# IV9.net
KiCad netlist of a schematic drawn in EAGLE
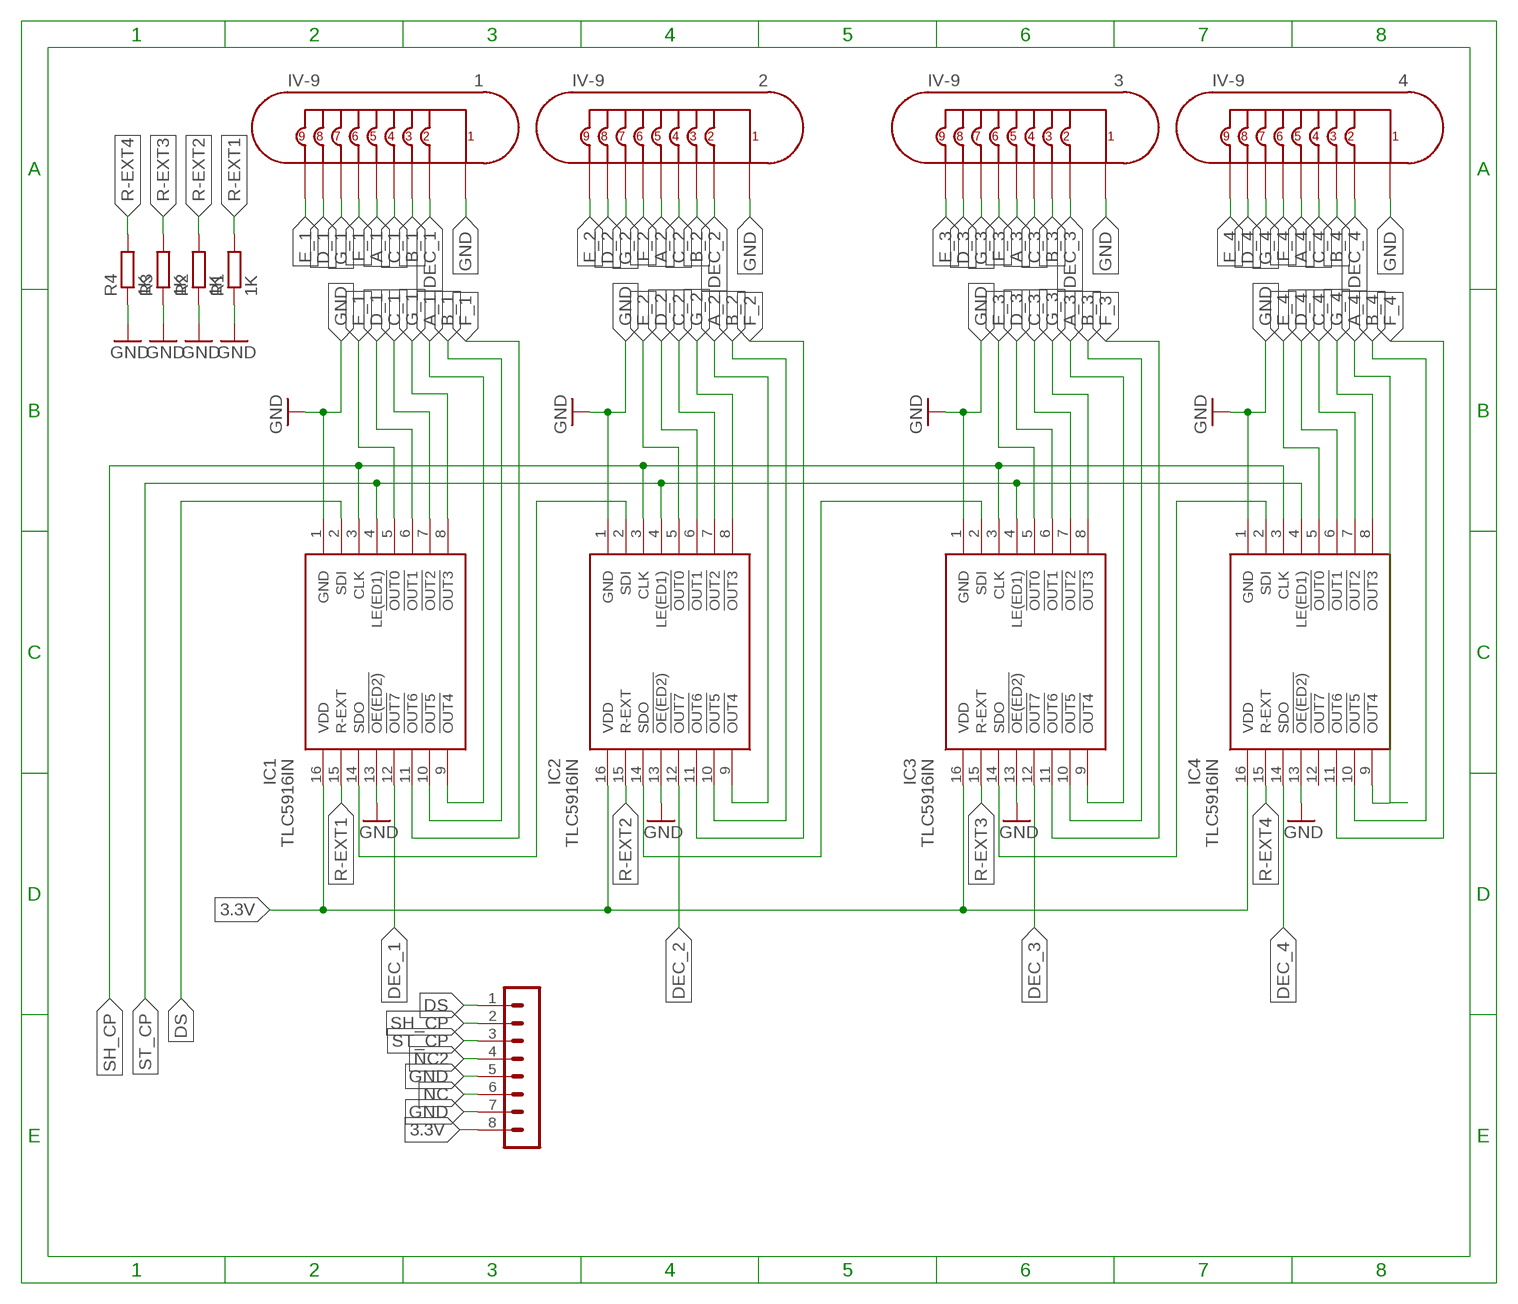
[diagram p0: schematic, sheet 1]

(export (version "E")
  (design (tool "Eeschema 10.0.6"))
  (components
    (comp (ref "1")
      (value "IV-9")
      (footprint "eagle-import:IV-9")
      (libsource (lib "eagle-import") (part "IV-9"))
    )
    (comp (ref "2")
      (value "IV-9")
      (footprint "eagle-import:IV-9")
      (libsource (lib "eagle-import") (part "IV-9"))
    )
    (comp (ref "3")
      (value "IV-9")
      (footprint "eagle-import:IV-9")
      (libsource (lib "eagle-import") (part "IV-9"))
    )
    (comp (ref "4")
      (value "IV-9")
      (footprint "eagle-import:IV-9")
      (libsource (lib "eagle-import") (part "IV-9"))
    )
    (comp (ref "IC1")
      (value "TLC5916IN")
      (footprint "eagle-import:DIP794W53P254L1930H508Q16N")
      (fields (field (name "MOUSER_PART_NUMBER") "595-TLC5916IN"))
      (libsource (lib "eagle-import") (part "TLC5916IN"))
    )
    (comp (ref "IC2")
      (value "TLC5916IN")
      (footprint "eagle-import:DIP794W53P254L1930H508Q16N")
      (fields (field (name "MOUSER_PART_NUMBER") "595-TLC5916IN"))
      (libsource (lib "eagle-import") (part "TLC5916IN"))
    )
    (comp (ref "IC3")
      (value "TLC5916IN")
      (footprint "eagle-import:DIP794W53P254L1930H508Q16N")
      (fields (field (name "MOUSER_PART_NUMBER") "595-TLC5916IN"))
      (libsource (lib "eagle-import") (part "TLC5916IN"))
    )
    (comp (ref "IC4")
      (value "TLC5916IN")
      (footprint "eagle-import:DIP794W53P254L1930H508Q16N")
      (fields (field (name "MOUSER_PART_NUMBER") "595-TLC5916IN"))
      (libsource (lib "eagle-import") (part "TLC5916IN"))
    )
    (comp (ref "R1")
      (value "1K")
      (footprint "eagle-import:R1206")
      (libsource (lib "eagle-import") (part "R-EU_R1206"))
    )
    (comp (ref "R2")
      (value "1K")
      (footprint "eagle-import:R1206")
      (libsource (lib "eagle-import") (part "R-EU_R1206"))
    )
    (comp (ref "R3")
      (value "1K")
      (footprint "eagle-import:R1206")
      (libsource (lib "eagle-import") (part "R-EU_R1206"))
    )
    (comp (ref "R4")
      (value "1K")
      (footprint "eagle-import:R1206")
      (libsource (lib "eagle-import") (part "R-EU_R1206"))
    )
    (comp (ref "SV2")
      (value "PINHEADER-1X8")
      (footprint "eagle-import:MA08-1")
      (libsource (lib "eagle-import") (part "PINHEADER-1X8"))
    )
  )
  (nets
    (net (code "1") (name "3.3V") (class "Default")
      (node (ref "IC1") (pin "16") (pinfunction "VDD_16") (pintype "bidirectional"))
      (node (ref "IC2") (pin "16") (pinfunction "VDD_16") (pintype "bidirectional"))
      (node (ref "IC3") (pin "16") (pinfunction "VDD_16") (pintype "bidirectional"))
      (node (ref "IC4") (pin "16") (pinfunction "VDD_16") (pintype "bidirectional"))
      (node (ref "SV2") (pin "8") (pinfunction "8_8") (pintype "passive"))
    )
    (net (code "2") (name "A_1") (class "Default")
      (node (ref "1") (pin "5") (pinfunction "5_5") (pintype "bidirectional"))
      (node (ref "IC1") (pin "9") (pinfunction "~{OUT4}_9") (pintype "bidirectional"))
    )
    (net (code "3") (name "A_2") (class "Default")
      (node (ref "2") (pin "5") (pinfunction "5_5") (pintype "bidirectional"))
      (node (ref "IC2") (pin "9") (pinfunction "~{OUT4}_9") (pintype "bidirectional"))
    )
    (net (code "4") (name "A_3") (class "Default")
      (node (ref "3") (pin "5") (pinfunction "5_5") (pintype "bidirectional"))
      (node (ref "IC3") (pin "9") (pinfunction "~{OUT4}_9") (pintype "bidirectional"))
    )
    (net (code "5") (name "A_4") (class "Default")
      (node (ref "4") (pin "5") (pinfunction "5_5") (pintype "bidirectional"))
      (node (ref "IC4") (pin "9") (pinfunction "~{OUT4}_9") (pintype "bidirectional"))
    )
    (net (code "6") (name "B_1") (class "Default")
      (node (ref "1") (pin "3") (pinfunction "3_3") (pintype "bidirectional"))
      (node (ref "IC1") (pin "10") (pinfunction "~{OUT5}_10") (pintype "bidirectional"))
    )
    (net (code "7") (name "B_2") (class "Default")
      (node (ref "2") (pin "3") (pinfunction "3_3") (pintype "bidirectional"))
      (node (ref "IC2") (pin "10") (pinfunction "~{OUT5}_10") (pintype "bidirectional"))
    )
    (net (code "8") (name "B_3") (class "Default")
      (node (ref "3") (pin "3") (pinfunction "3_3") (pintype "bidirectional"))
      (node (ref "IC3") (pin "10") (pinfunction "~{OUT5}_10") (pintype "bidirectional"))
    )
    (net (code "9") (name "B_4") (class "Default")
      (node (ref "4") (pin "3") (pinfunction "3_3") (pintype "bidirectional"))
      (node (ref "IC4") (pin "10") (pinfunction "~{OUT5}_10") (pintype "bidirectional"))
    )
    (net (code "10") (name "C_1") (class "Default")
      (node (ref "1") (pin "4") (pinfunction "4_4") (pintype "bidirectional"))
      (node (ref "IC1") (pin "7") (pinfunction "~{OUT2}_7") (pintype "bidirectional"))
    )
    (net (code "11") (name "C_2") (class "Default")
      (node (ref "2") (pin "4") (pinfunction "4_4") (pintype "bidirectional"))
      (node (ref "IC2") (pin "7") (pinfunction "~{OUT2}_7") (pintype "bidirectional"))
    )
    (net (code "12") (name "C_3") (class "Default")
      (node (ref "3") (pin "4") (pinfunction "4_4") (pintype "bidirectional"))
      (node (ref "IC3") (pin "7") (pinfunction "~{OUT2}_7") (pintype "bidirectional"))
    )
    (net (code "13") (name "C_4") (class "Default")
      (node (ref "4") (pin "4") (pinfunction "4_4") (pintype "bidirectional"))
      (node (ref "IC4") (pin "7") (pinfunction "~{OUT2}_7") (pintype "bidirectional"))
    )
    (net (code "14") (name "DEC_1") (class "Default")
      (node (ref "1") (pin "2") (pinfunction "2_2") (pintype "bidirectional"))
      (node (ref "IC1") (pin "12") (pinfunction "~{OUT7}_12") (pintype "bidirectional"))
    )
    (net (code "15") (name "DEC_2") (class "Default")
      (node (ref "2") (pin "2") (pinfunction "2_2") (pintype "bidirectional"))
      (node (ref "IC2") (pin "12") (pinfunction "~{OUT7}_12") (pintype "bidirectional"))
    )
    (net (code "16") (name "DEC_3") (class "Default")
      (node (ref "3") (pin "2") (pinfunction "2_2") (pintype "bidirectional"))
      (node (ref "IC3") (pin "12") (pinfunction "~{OUT7}_12") (pintype "bidirectional"))
    )
    (net (code "17") (name "DEC_4") (class "Default")
      (node (ref "4") (pin "2") (pinfunction "2_2") (pintype "bidirectional"))
      (node (ref "IC4") (pin "14") (pinfunction "SDO_14") (pintype "bidirectional"))
    )
    (net (code "18") (name "DS") (class "Default")
      (node (ref "IC1") (pin "2") (pinfunction "SDI_2") (pintype "bidirectional"))
      (node (ref "SV2") (pin "1") (pinfunction "1_1") (pintype "passive"))
    )
    (net (code "19") (name "D_1") (class "Default")
      (node (ref "1") (pin "8") (pinfunction "8_8") (pintype "bidirectional"))
      (node (ref "IC1") (pin "6") (pinfunction "~{OUT1}_6") (pintype "bidirectional"))
    )
    (net (code "20") (name "D_2") (class "Default")
      (node (ref "2") (pin "8") (pinfunction "8_8") (pintype "bidirectional"))
      (node (ref "IC2") (pin "6") (pinfunction "~{OUT1}_6") (pintype "bidirectional"))
    )
    (net (code "21") (name "D_3") (class "Default")
      (node (ref "3") (pin "8") (pinfunction "8_8") (pintype "bidirectional"))
      (node (ref "IC3") (pin "6") (pinfunction "~{OUT1}_6") (pintype "bidirectional"))
    )
    (net (code "22") (name "D_4") (class "Default")
      (node (ref "4") (pin "8") (pinfunction "8_8") (pintype "bidirectional"))
      (node (ref "IC4") (pin "6") (pinfunction "~{OUT1}_6") (pintype "bidirectional"))
    )
    (net (code "23") (name "E_1") (class "Default")
      (node (ref "1") (pin "9") (pinfunction "9_9") (pintype "bidirectional"))
      (node (ref "IC1") (pin "5") (pinfunction "~{OUT0}_5") (pintype "bidirectional"))
    )
    (net (code "24") (name "E_2") (class "Default")
      (node (ref "2") (pin "9") (pinfunction "9_9") (pintype "bidirectional"))
      (node (ref "IC2") (pin "5") (pinfunction "~{OUT0}_5") (pintype "bidirectional"))
    )
    (net (code "25") (name "E_3") (class "Default")
      (node (ref "3") (pin "9") (pinfunction "9_9") (pintype "bidirectional"))
      (node (ref "IC3") (pin "5") (pinfunction "~{OUT0}_5") (pintype "bidirectional"))
    )
    (net (code "26") (name "E_4") (class "Default")
      (node (ref "4") (pin "9") (pinfunction "9_9") (pintype "bidirectional"))
      (node (ref "IC4") (pin "5") (pinfunction "~{OUT0}_5") (pintype "bidirectional"))
    )
    (net (code "27") (name "F_1") (class "Default")
      (node (ref "1") (pin "6") (pinfunction "6_6") (pintype "bidirectional"))
      (node (ref "IC1") (pin "11") (pinfunction "~{OUT6}_11") (pintype "bidirectional"))
    )
    (net (code "28") (name "F_2") (class "Default")
      (node (ref "2") (pin "6") (pinfunction "6_6") (pintype "bidirectional"))
      (node (ref "IC2") (pin "11") (pinfunction "~{OUT6}_11") (pintype "bidirectional"))
    )
    (net (code "29") (name "F_3") (class "Default")
      (node (ref "3") (pin "6") (pinfunction "6_6") (pintype "bidirectional"))
      (node (ref "IC3") (pin "11") (pinfunction "~{OUT6}_11") (pintype "bidirectional"))
    )
    (net (code "30") (name "F_4") (class "Default")
      (node (ref "4") (pin "6") (pinfunction "6_6") (pintype "bidirectional"))
      (node (ref "IC4") (pin "11") (pinfunction "~{OUT6}_11") (pintype "bidirectional"))
    )
    (net (code "31") (name "GND") (class "Default")
      (node (ref "1") (pin "1") (pinfunction "1_1") (pintype "bidirectional"))
      (node (ref "2") (pin "1") (pinfunction "1_1") (pintype "bidirectional"))
      (node (ref "3") (pin "1") (pinfunction "1_1") (pintype "bidirectional"))
      (node (ref "4") (pin "1") (pinfunction "1_1") (pintype "bidirectional"))
      (node (ref "IC1") (pin "1") (pinfunction "GND_1") (pintype "bidirectional"))
      (node (ref "IC1") (pin "13") (pinfunction "~{OE(ED2})_13") (pintype "bidirectional"))
      (node (ref "IC2") (pin "1") (pinfunction "GND_1") (pintype "bidirectional"))
      (node (ref "IC2") (pin "13") (pinfunction "~{OE(ED2})_13") (pintype "bidirectional"))
      (node (ref "IC3") (pin "1") (pinfunction "GND_1") (pintype "bidirectional"))
      (node (ref "IC3") (pin "13") (pinfunction "~{OE(ED2})_13") (pintype "bidirectional"))
      (node (ref "IC4") (pin "1") (pinfunction "GND_1") (pintype "bidirectional"))
      (node (ref "IC4") (pin "13") (pinfunction "~{OE(ED2})_13") (pintype "bidirectional"))
      (node (ref "R1") (pin "1") (pinfunction "1_1") (pintype "passive"))
      (node (ref "R2") (pin "1") (pinfunction "1_1") (pintype "passive"))
      (node (ref "R3") (pin "1") (pinfunction "1_1") (pintype "passive"))
      (node (ref "R4") (pin "1") (pinfunction "1_1") (pintype "passive"))
      (node (ref "SV2") (pin "5") (pinfunction "5_5") (pintype "passive"))
      (node (ref "SV2") (pin "7") (pinfunction "7_7") (pintype "passive"))
    )
    (net (code "32") (name "G_1") (class "Default")
      (node (ref "1") (pin "7") (pinfunction "7_7") (pintype "bidirectional"))
      (node (ref "IC1") (pin "8") (pinfunction "~{OUT3}_8") (pintype "bidirectional"))
    )
    (net (code "33") (name "G_2") (class "Default")
      (node (ref "2") (pin "7") (pinfunction "7_7") (pintype "bidirectional"))
      (node (ref "IC2") (pin "8") (pinfunction "~{OUT3}_8") (pintype "bidirectional"))
    )
    (net (code "34") (name "G_3") (class "Default")
      (node (ref "3") (pin "7") (pinfunction "7_7") (pintype "bidirectional"))
      (node (ref "IC3") (pin "8") (pinfunction "~{OUT3}_8") (pintype "bidirectional"))
    )
    (net (code "35") (name "G_4") (class "Default")
      (node (ref "4") (pin "7") (pinfunction "7_7") (pintype "bidirectional"))
      (node (ref "IC4") (pin "8") (pinfunction "~{OUT3}_8") (pintype "bidirectional"))
    )
    (net (code "36") (name "NC") (class "Default")
      (node (ref "SV2") (pin "6") (pinfunction "6_6") (pintype "passive"))
    )
    (net (code "37") (name "NC2") (class "Default")
      (node (ref "SV2") (pin "4") (pinfunction "4_4") (pintype "passive"))
    )
    (net (code "38") (name "Net-(IC1-SDO)") (class "Default")
      (node (ref "IC1") (pin "14") (pinfunction "SDO_14") (pintype "bidirectional"))
      (node (ref "IC2") (pin "2") (pinfunction "SDI_2") (pintype "bidirectional"))
    )
    (net (code "39") (name "Net-(IC2-SDO)") (class "Default")
      (node (ref "IC2") (pin "14") (pinfunction "SDO_14") (pintype "bidirectional"))
      (node (ref "IC3") (pin "2") (pinfunction "SDI_2") (pintype "bidirectional"))
    )
    (net (code "40") (name "Net-(IC3-SDO)") (class "Default")
      (node (ref "IC3") (pin "14") (pinfunction "SDO_14") (pintype "bidirectional"))
      (node (ref "IC4") (pin "2") (pinfunction "SDI_2") (pintype "bidirectional"))
    )
    (net (code "41") (name "R-EXT1") (class "Default")
      (node (ref "IC1") (pin "15") (pinfunction "R-EXT_15") (pintype "bidirectional"))
      (node (ref "R1") (pin "2") (pinfunction "2_2") (pintype "passive"))
    )
    (net (code "42") (name "R-EXT2") (class "Default")
      (node (ref "IC2") (pin "15") (pinfunction "R-EXT_15") (pintype "bidirectional"))
      (node (ref "R2") (pin "2") (pinfunction "2_2") (pintype "passive"))
    )
    (net (code "43") (name "R-EXT3") (class "Default")
      (node (ref "IC3") (pin "15") (pinfunction "R-EXT_15") (pintype "bidirectional"))
      (node (ref "R3") (pin "2") (pinfunction "2_2") (pintype "passive"))
    )
    (net (code "44") (name "R-EXT4") (class "Default")
      (node (ref "IC4") (pin "15") (pinfunction "R-EXT_15") (pintype "bidirectional"))
      (node (ref "R4") (pin "2") (pinfunction "2_2") (pintype "passive"))
    )
    (net (code "45") (name "SH_CP") (class "Default")
      (node (ref "IC1") (pin "3") (pinfunction "CLK_3") (pintype "bidirectional"))
      (node (ref "IC2") (pin "3") (pinfunction "CLK_3") (pintype "bidirectional"))
      (node (ref "IC3") (pin "3") (pinfunction "CLK_3") (pintype "bidirectional"))
      (node (ref "IC4") (pin "3") (pinfunction "CLK_3") (pintype "bidirectional"))
      (node (ref "SV2") (pin "2") (pinfunction "2_2") (pintype "passive"))
    )
    (net (code "46") (name "ST_CP") (class "Default")
      (node (ref "IC1") (pin "4") (pinfunction "LE(ED1)_4") (pintype "bidirectional"))
      (node (ref "IC2") (pin "4") (pinfunction "LE(ED1)_4") (pintype "bidirectional"))
      (node (ref "IC3") (pin "4") (pinfunction "LE(ED1)_4") (pintype "bidirectional"))
      (node (ref "IC4") (pin "4") (pinfunction "LE(ED1)_4") (pintype "bidirectional"))
      (node (ref "SV2") (pin "3") (pinfunction "3_3") (pintype "passive"))
    )
    (net (code "47") (name "unconnected-(IC4-~{OUT7}-Pad12)") (class "Default")
      (node (ref "IC4") (pin "12") (pinfunction "~{OUT7}_12") (pintype "bidirectional"))
    )
  )
)
